# PowerUnit.net
KiCad netlist of a schematic drawn in Altium Designer
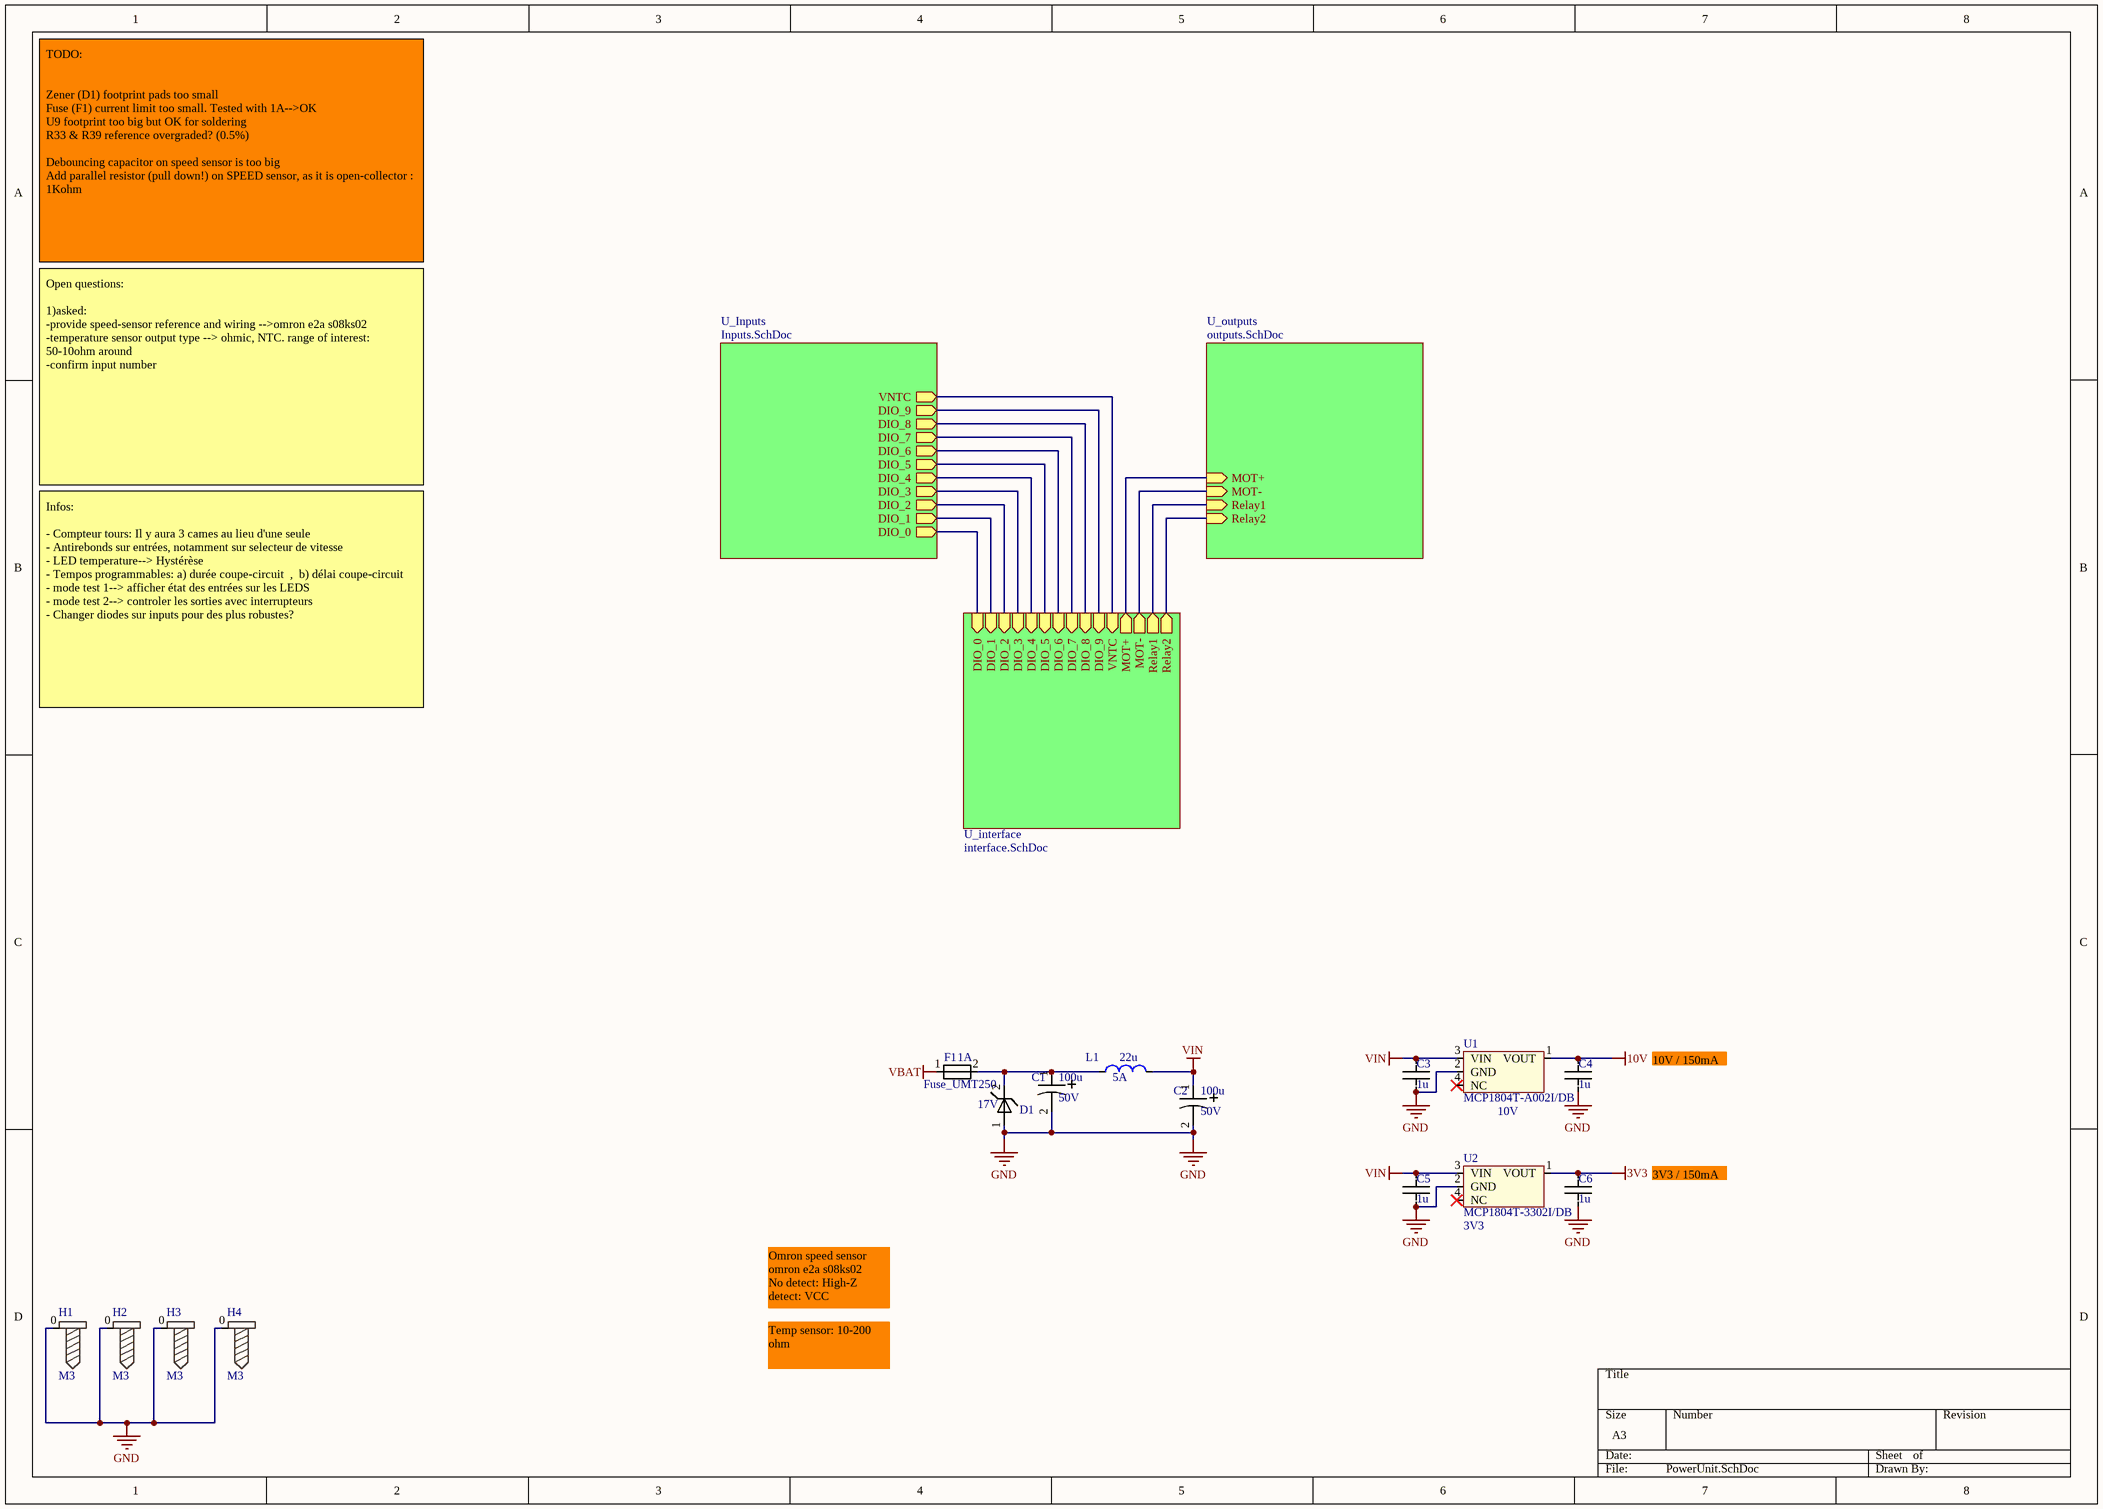
[diagram p0: PowerUnit.SchDoc]

(export (version "E")
  (design (tool "Eeschema 10.0.6"))
  (components
    (comp (ref "C1")
      (value "100u")
      (footprint "C_pol8x12mm")
      (fields
        (field (name "RATED VOLTAGE") "50V")
        (field (name "MANUFACTURER") "Nichicon")
        (field (name "MANUFACTURER PARTNUM") "UVR1H101MPD1TD")
        (field (name "Comment") "C_pol")
      )
      (libsource (lib "Sch_GB_lib") (part "C_pol"))
    )
    (comp (ref "C2")
      (value "100u")
      (footprint "C_pol8x12mm")
      (fields
        (field (name "RATED VOLTAGE") "50V")
        (field (name "MANUFACTURER") "Nichicon")
        (field (name "MANUFACTURER PARTNUM") "UVR1H101MPD1TD")
        (field (name "Comment") "C_pol")
      )
      (libsource (lib "Sch_GB_lib") (part "C_pol"))
    )
    (comp (ref "C3")
      (value "1u")
      (footprint "0402_")
      (fields
        (field (name "MANUFACTURER PARTNUM") "GRM155R61E105MA12D")
        (field (name "MANUFACTURER") "Murata")
      )
      (libsource (lib "*") (part "C"))
    )
    (comp (ref "C4")
      (value "1u")
      (footprint "0402_")
      (fields
        (field (name "MANUFACTURER PARTNUM") "GRM155R61E105MA12D")
        (field (name "MANUFACTURER") "Murata")
      )
      (libsource (lib "*") (part "C"))
    )
    (comp (ref "C5")
      (value "1u")
      (footprint "0402_")
      (fields
        (field (name "MANUFACTURER PARTNUM") "GRM155R61E105MA12D")
        (field (name "MANUFACTURER") "Murata")
      )
      (libsource (lib "*") (part "C"))
    )
    (comp (ref "C6")
      (value "1u")
      (footprint "0402_")
      (fields
        (field (name "MANUFACTURER PARTNUM") "GRM155R61E105MA12D")
        (field (name "MANUFACTURER") "Murata")
      )
      (libsource (lib "*") (part "C"))
    )
    (comp (ref "D1")
      (value "Zener")
      (footprint "R_DIL_vertical_holes1_2mm")
      (fields
        (field (name "VZ") "17V")
        (field (name "MANUFACTURER") "ON Semi")
        (field (name "MANUFACTURER PARTNUM") "1N5354BG")
      )
      (libsource (lib "Sch_GB_lib") (part "Zener"))
    )
    (comp (ref "F1")
      (value "Fuse_UMT250")
      (footprint "FUSE_UMT250")
      (fields
        (field (name "CALIBRE") "1A")
        (field (name "MANUFACTURER PARTNUM") "3403.0166.11")
        (field (name "MANUFACTURER") "Schurter Inc")
      )
      (libsource (lib "Sch_GB_lib") (part "Fuse_UMT250"))
    )
    (comp (ref "H1")
      (value "M3")
      (footprint "Mechanical_hole")
      (libsource (lib "Sch_GB_lib") (part "trous_de_fixation"))
    )
    (comp (ref "H2")
      (value "M3")
      (footprint "Mechanical_hole")
      (libsource (lib "Sch_GB_lib") (part "trous_de_fixation"))
    )
    (comp (ref "H3")
      (value "M3")
      (footprint "Mechanical_hole")
      (libsource (lib "Sch_GB_lib") (part "trous_de_fixation"))
    )
    (comp (ref "H4")
      (value "M3")
      (footprint "Mechanical_hole")
      (libsource (lib "Sch_GB_lib") (part "trous_de_fixation"))
    )
    (comp (ref "L1")
      (value "22u")
      (footprint "WURTH_7447709220")
      (fields
        (field (name "CURRENT") "5A")
        (field (name "MANUFACTURER PARTNUM") "7447709220")
        (field (name "MANUFACTURER") "Wurth Electronics Inc")
        (field (name "Comment") "Inductor")
      )
      (libsource (lib "Sch_GB_lib") (part "Inductor"))
    )
    (comp (ref "U1")
      (value "MCP1804T-A002I/DB")
      (footprint "SOT223-4M")
      (description "IC REG LDO 10V 0.15A SOT223-3")
      (fields (field (name "MANUFACTURER") "Microchip") (field (name "OUTPUT VOLTAGE") "10V"))
      (libsource (lib "Sch_GB_lib") (part "MCP1804T-A002I/DB"))
    )
    (comp (ref "U2")
      (value "MCP1804T-3302I/DB")
      (footprint "SOT223-4M")
      (description "IC REG LDO 3.3V 0.15A SOT223-3")
      (fields (field (name "MANUFACTURER") "Microchip") (field (name "OUTPUT VOLTAGE") "3V3"))
      (libsource (lib "Sch_GB_lib") (part "MCP1804T-3302I/DB"))
    )
  )
  (nets
    (net (code "16") (name "3V3") (class "Default")
      (node (ref "C6") (pin "1") (pinfunction "1_1") (pintype "passive"))
      (node (ref "U2") (pin "1") (pinfunction "VOUT_1") (pintype "passive"))
    )
    (net (code "17") (name "10V") (class "Default")
      (node (ref "C4") (pin "1") (pinfunction "1_1") (pintype "passive"))
      (node (ref "U1") (pin "1") (pinfunction "VOUT_1") (pintype "passive"))
    )
    (net (code "18") (name "GND") (class "Default")
      (node (ref "C1") (pin "2") (pinfunction "2_2") (pintype "passive"))
      (node (ref "C2") (pin "2") (pinfunction "2_2") (pintype "passive"))
      (node (ref "C3") (pin "2") (pinfunction "2_2") (pintype "passive"))
      (node (ref "C4") (pin "2") (pinfunction "2_2") (pintype "passive"))
      (node (ref "C5") (pin "2") (pinfunction "2_2") (pintype "passive"))
      (node (ref "C6") (pin "2") (pinfunction "2_2") (pintype "passive"))
      (node (ref "D1") (pin "1") (pinfunction "1_1") (pintype "passive"))
      (node (ref "H1") (pin "0") (pinfunction "0_0") (pintype "passive"))
      (node (ref "H2") (pin "0") (pinfunction "0_0") (pintype "passive"))
      (node (ref "H3") (pin "0") (pinfunction "0_0") (pintype "passive"))
      (node (ref "H4") (pin "0") (pinfunction "0_0") (pintype "passive"))
      (node (ref "U1") (pin "2") (pinfunction "GND_2") (pintype "passive"))
      (node (ref "U2") (pin "2") (pinfunction "GND_2") (pintype "passive"))
    )
    (net (code "19") (name "Net-(C1-Pad1)") (class "Default")
      (node (ref "C1") (pin "1") (pinfunction "1_1") (pintype "passive"))
      (node (ref "D1") (pin "2") (pinfunction "2_2") (pintype "passive"))
      (node (ref "F1") (pin "2") (pinfunction "2_2") (pintype "passive"))
      (node (ref "L1") (pin "1") (pinfunction "1_1") (pintype "passive"))
    )
    (net (code "20") (name "VBAT") (class "Default")
      (node (ref "F1") (pin "1") (pinfunction "1_1") (pintype "passive"))
    )
    (net (code "21") (name "VIN") (class "Default")
      (node (ref "C2") (pin "1") (pinfunction "1_1") (pintype "passive"))
      (node (ref "C3") (pin "1") (pinfunction "1_1") (pintype "passive"))
      (node (ref "C5") (pin "1") (pinfunction "1_1") (pintype "passive"))
      (node (ref "L1") (pin "2") (pinfunction "2_2") (pintype "passive"))
      (node (ref "U1") (pin "3") (pinfunction "VIN_3") (pintype "passive"))
      (node (ref "U2") (pin "3") (pinfunction "VIN_3") (pintype "passive"))
    )
    (net (code "22") (name "unconnected-(U1-NC-Pad4)") (class "Default")
      (node (ref "U1") (pin "4") (pinfunction "NC_4") (pintype "passive+no_connect"))
    )
    (net (code "23") (name "unconnected-(U2-NC-Pad4)") (class "Default")
      (node (ref "U2") (pin "4") (pinfunction "NC_4") (pintype "passive+no_connect"))
    )
  )
)
